# SCH.net
KiCad netlist of a schematic drawn in Altium Designer
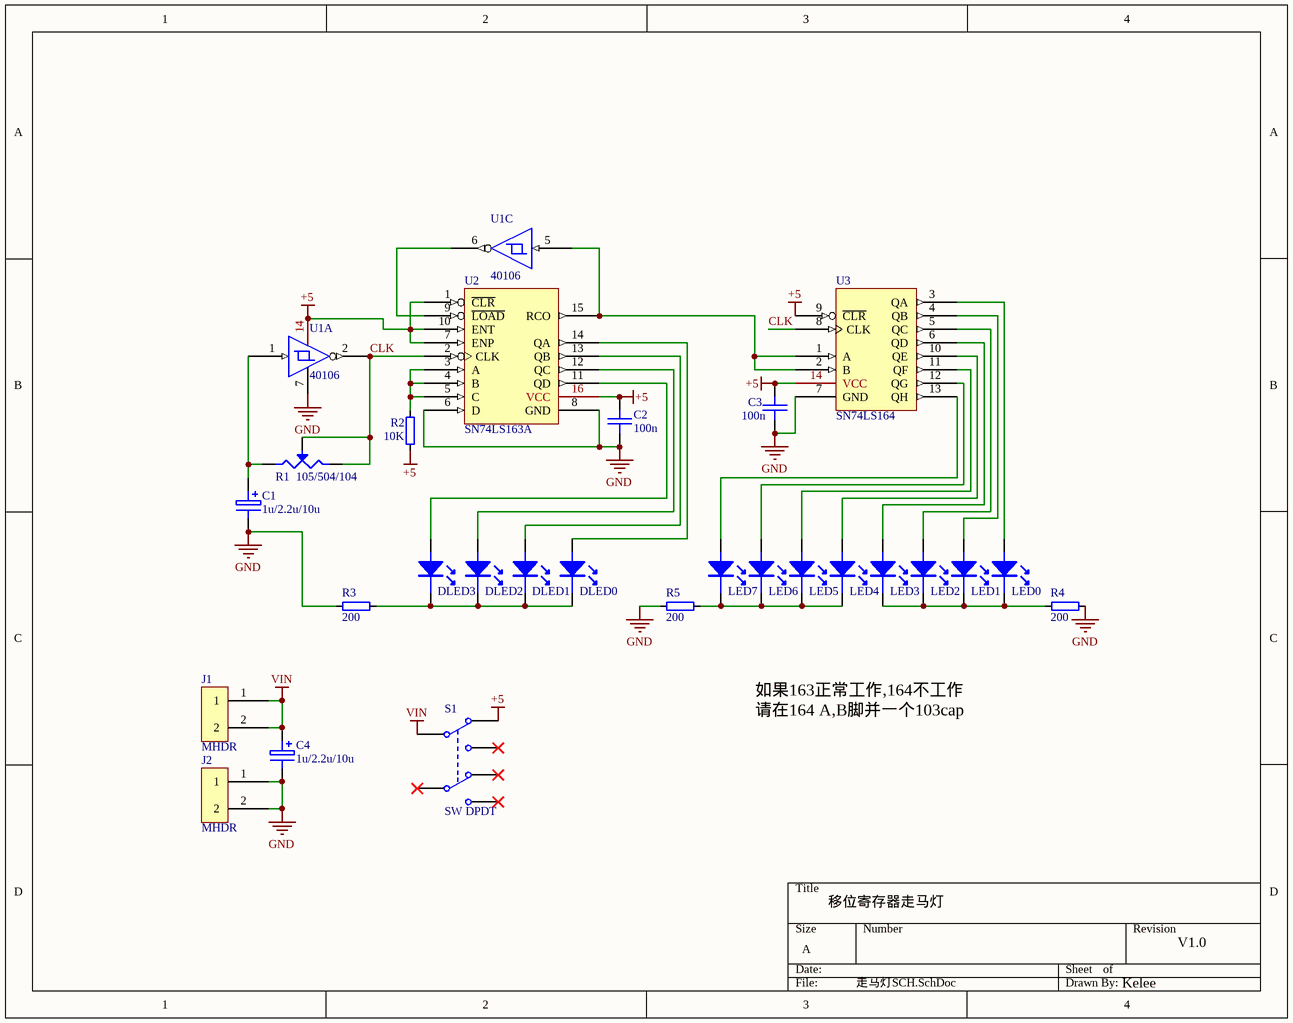
[diagram p0: 走马灯SCH.SchDoc]

(export (version "E")
  (design (tool "Eeschema 10.0.6"))
  (components
    (comp (ref "C1")
      (value "1u/2.2u/10u")
      (footprint "插件电容，贴片电容:C5X8")
      (description "电解电容")
      (libsource (lib "走马灯SCH") (part "CAP-E"))
    )
    (comp (ref "C2")
      (value "100n")
      (footprint "插件电容，贴片电容:MLCC5.08-A")
      (description "独石电容")
      (libsource (lib "走马灯SCH") (part "CAP-M"))
    )
    (comp (ref "C3")
      (value "100n")
      (footprint "插件电容，贴片电容:MLCC5.08-A")
      (description "独石电容")
      (libsource (lib "走马灯SCH") (part "CAP-M"))
    )
    (comp (ref "C4")
      (value "1u/2.2u/10u")
      (footprint "插件电容，贴片电容:C5X8")
      (description "电解电容")
      (libsource (lib "走马灯SCH") (part "CAP-E"))
    )
    (comp (ref "DLED0")
      (value "D-LED")
      (footprint "LED,数码管,显示屏,点阵,蜂鸣器:LED 5MM-Y")
      (description "LED")
      (libsource (lib "走马灯SCH") (part "D-LED"))
    )
    (comp (ref "DLED1")
      (value "D-LED")
      (footprint "LED,数码管,显示屏,点阵,蜂鸣器:LED 5MM-Y")
      (description "LED")
      (libsource (lib "走马灯SCH") (part "D-LED"))
    )
    (comp (ref "DLED2")
      (value "D-LED")
      (footprint "LED,数码管,显示屏,点阵,蜂鸣器:LED 5MM-Y")
      (description "LED")
      (libsource (lib "走马灯SCH") (part "D-LED"))
    )
    (comp (ref "DLED3")
      (value "D-LED")
      (footprint "LED,数码管,显示屏,点阵,蜂鸣器:LED 5MM-Y")
      (description "LED")
      (libsource (lib "走马灯SCH") (part "D-LED"))
    )
    (comp (ref "J1")
      (value "MHDR")
      (footprint "走马灯PCB:HDR1X2")
      (description "MHDR1x2")
      (libsource (lib "走马灯SCH") (part "MHDR1x2"))
    )
    (comp (ref "J2")
      (value "MHDR")
      (footprint "走马灯PCB:HDR1X2")
      (description "MHDR1x2")
      (libsource (lib "走马灯SCH") (part "MHDR1x2"))
    )
    (comp (ref "LED0")
      (value "LED")
      (footprint "LED,数码管,显示屏,点阵,蜂鸣器:LED 5MM-R")
      (libsource (lib "走马灯SCH") (part "LED"))
    )
    (comp (ref "LED1")
      (value "LED")
      (footprint "LED,数码管,显示屏,点阵,蜂鸣器:LED 5MM-R")
      (libsource (lib "走马灯SCH") (part "LED"))
    )
    (comp (ref "LED2")
      (value "LED")
      (footprint "LED,数码管,显示屏,点阵,蜂鸣器:LED 5MM-R")
      (libsource (lib "走马灯SCH") (part "LED"))
    )
    (comp (ref "LED3")
      (value "LED")
      (footprint "LED,数码管,显示屏,点阵,蜂鸣器:LED 5MM-R")
      (libsource (lib "走马灯SCH") (part "LED"))
    )
    (comp (ref "LED4")
      (value "LED")
      (footprint "LED,数码管,显示屏,点阵,蜂鸣器:LED 5MM-R")
      (libsource (lib "走马灯SCH") (part "LED"))
    )
    (comp (ref "LED5")
      (value "LED")
      (footprint "LED,数码管,显示屏,点阵,蜂鸣器:LED 5MM-R")
      (libsource (lib "走马灯SCH") (part "LED"))
    )
    (comp (ref "LED6")
      (value "LED")
      (footprint "LED,数码管,显示屏,点阵,蜂鸣器:LED 5MM-R")
      (libsource (lib "走马灯SCH") (part "LED"))
    )
    (comp (ref "LED7")
      (value "LED")
      (footprint "LED,数码管,显示屏,点阵,蜂鸣器:LED 5MM-R")
      (libsource (lib "走马灯SCH") (part "LED"))
    )
    (comp (ref "R1")
      (value "105/504/104")
      (footprint "电阻插件贴片排阻:RES ADJ3")
      (libsource (lib "走马灯SCH") (part "R-GLIDE"))
    )
    (comp (ref "R2")
      (value "10K")
      (footprint "电阻插件贴片排阻:RS 1/4W")
      (description "resistor")
      (libsource (lib "走马灯SCH") (part "R-10K"))
    )
    (comp (ref "R3")
      (value "200")
      (footprint "电阻插件贴片排阻:RS 1/4W")
      (description "resistor")
      (libsource (lib "走马灯SCH") (part "R-200"))
    )
    (comp (ref "R4")
      (value "200")
      (footprint "电阻插件贴片排阻:RS 1/4W")
      (description "resistor")
      (libsource (lib "走马灯SCH") (part "R-200"))
    )
    (comp (ref "R5")
      (value "200")
      (footprint "电阻插件贴片排阻:RS 1/4W")
      (description "resistor")
      (libsource (lib "走马灯SCH") (part "R-200"))
    )
    (comp (ref "S1")
      (value "SW DPDT")
      (footprint "走马灯PCB:KFT DIP-8X8")
      (description "Switch")
      (fields (field (name "PUBLISHER") "Altium Limited"))
      (libsource (lib "走马灯SCH") (part "SW DPDT"))
    )
    (comp (ref "U1") (value "40106") (footprint "IC:DIP14") (libsource (lib "走马灯SCH") (part "CD40106")))
    (comp (ref "U2")
      (value "SN74LS163A")
      (footprint "IC:DIP16")
      (description "SYN 4-BIT CNT")
      (libsource (lib "走马灯SCH") (part "SN74LS163A"))
    )
    (comp (ref "U3")
      (value "SN74LS164")
      (footprint "IC:DIP14")
      (description "8-BIT PALL SERI SFT REG")
      (libsource (lib "走马灯SCH") (part "SN74LS164"))
    )
  )
  (nets
    (net (code "1") (name "+5") (class "Default")
      (node (ref "C2") (pin "2") (pinfunction "2_2") (pintype "passive"))
      (node (ref "C3") (pin "2") (pinfunction "2_2") (pintype "passive"))
      (node (ref "R2") (pin "2") (pinfunction "2_2") (pintype "passive"))
      (node (ref "S1") (pin "1") (pinfunction "NC1_1") (pintype "passive"))
      (node (ref "U1") (pin "14") (pinfunction "Vdd_14") (pintype "passive"))
      (node (ref "U2") (pin "1") (pinfunction "~{CLR}_1") (pintype "input"))
      (node (ref "U2") (pin "10") (pinfunction "ENT_10") (pintype "input"))
      (node (ref "U2") (pin "16") (pinfunction "VCC_16") (pintype "passive"))
      (node (ref "U2") (pin "7") (pinfunction "ENP_7") (pintype "input"))
      (node (ref "U3") (pin "14") (pinfunction "VCC_14") (pintype "passive"))
      (node (ref "U3") (pin "9") (pinfunction "~{CLR}_9") (pintype "input"))
    )
    (net (code "2") (name "/CLK") (class "Default")
      (node (ref "R1") (pin "2") (pinfunction "2_2") (pintype "passive"))
      (node (ref "R1") (pin "3") (pinfunction "W_3") (pintype "passive"))
      (node (ref "U1") (pin "2") (pintype "output"))
      (node (ref "U2") (pin "2") (pinfunction "CLK_2") (pintype "input"))
      (node (ref "U3") (pin "8") (pinfunction "CLK_8") (pintype "input"))
    )
    (net (code "3") (name "GND") (class "Default")
      (node (ref "C1") (pin "2") (pinfunction "2_2") (pintype "passive"))
      (node (ref "C2") (pin "1") (pinfunction "1_1") (pintype "passive"))
      (node (ref "C3") (pin "1") (pinfunction "1_1") (pintype "passive"))
      (node (ref "C4") (pin "2") (pinfunction "2_2") (pintype "passive"))
      (node (ref "J2") (pin "1") (pinfunction "1_1") (pintype "passive"))
      (node (ref "J2") (pin "2") (pinfunction "2_2") (pintype "passive"))
      (node (ref "R3") (pin "1") (pinfunction "1_1") (pintype "passive"))
      (node (ref "R4") (pin "2") (pinfunction "2_2") (pintype "passive"))
      (node (ref "R5") (pin "1") (pinfunction "1_1") (pintype "passive"))
      (node (ref "U1") (pin "7") (pinfunction "GND_7") (pintype "power_in"))
      (node (ref "U2") (pin "6") (pinfunction "D_6") (pintype "input"))
      (node (ref "U2") (pin "8") (pinfunction "GND_8") (pintype "power_in"))
      (node (ref "U3") (pin "7") (pinfunction "GND_7") (pintype "passive"))
    )
    (net (code "4") (name "Net-(C1-Pad1)") (class "Default")
      (node (ref "C1") (pin "1") (pinfunction "1_1") (pintype "passive"))
      (node (ref "R1") (pin "1") (pinfunction "1_1") (pintype "passive"))
      (node (ref "U1") (pin "1") (pintype "input"))
    )
    (net (code "5") (name "Net-(DLED0-A)") (class "Default")
      (node (ref "DLED0") (pin "1") (pinfunction "A_1") (pintype "passive"))
      (node (ref "U2") (pin "14") (pinfunction "QA_14") (pintype "output"))
    )
    (net (code "6") (name "Net-(DLED0-K)") (class "Default")
      (node (ref "DLED0") (pin "2") (pinfunction "K_2") (pintype "passive"))
      (node (ref "DLED1") (pin "2") (pinfunction "K_2") (pintype "passive"))
      (node (ref "DLED2") (pin "2") (pinfunction "K_2") (pintype "passive"))
      (node (ref "DLED3") (pin "2") (pinfunction "K_2") (pintype "passive"))
      (node (ref "R3") (pin "2") (pinfunction "2_2") (pintype "passive"))
    )
    (net (code "7") (name "Net-(DLED1-A)") (class "Default")
      (node (ref "DLED1") (pin "1") (pinfunction "A_1") (pintype "passive"))
      (node (ref "U2") (pin "13") (pinfunction "QB_13") (pintype "output"))
    )
    (net (code "8") (name "Net-(DLED2-A)") (class "Default")
      (node (ref "DLED2") (pin "1") (pinfunction "A_1") (pintype "passive"))
      (node (ref "U2") (pin "12") (pinfunction "QC_12") (pintype "output"))
    )
    (net (code "9") (name "Net-(DLED3-A)") (class "Default")
      (node (ref "DLED3") (pin "1") (pinfunction "A_1") (pintype "passive"))
      (node (ref "U2") (pin "11") (pinfunction "QD_11") (pintype "output"))
    )
    (net (code "10") (name "Net-(LED0-A)") (class "Default")
      (node (ref "LED0") (pin "1") (pinfunction "A_1") (pintype "passive"))
      (node (ref "U3") (pin "3") (pinfunction "QA_3") (pintype "output"))
    )
    (net (code "11") (name "Net-(LED0-K)") (class "Default")
      (node (ref "LED0") (pin "2") (pinfunction "K_2") (pintype "passive"))
      (node (ref "LED1") (pin "2") (pinfunction "K_2") (pintype "passive"))
      (node (ref "LED2") (pin "2") (pinfunction "K_2") (pintype "passive"))
      (node (ref "LED3") (pin "2") (pinfunction "K_2") (pintype "passive"))
      (node (ref "R4") (pin "1") (pinfunction "1_1") (pintype "passive"))
    )
    (net (code "12") (name "Net-(LED1-A)") (class "Default")
      (node (ref "LED1") (pin "1") (pinfunction "A_1") (pintype "passive"))
      (node (ref "U3") (pin "4") (pinfunction "QB_4") (pintype "output"))
    )
    (net (code "13") (name "Net-(LED2-A)") (class "Default")
      (node (ref "LED2") (pin "1") (pinfunction "A_1") (pintype "passive"))
      (node (ref "U3") (pin "5") (pinfunction "QC_5") (pintype "output"))
    )
    (net (code "14") (name "Net-(LED3-A)") (class "Default")
      (node (ref "LED3") (pin "1") (pinfunction "A_1") (pintype "passive"))
      (node (ref "U3") (pin "6") (pinfunction "QD_6") (pintype "output"))
    )
    (net (code "15") (name "Net-(LED4-A)") (class "Default")
      (node (ref "LED4") (pin "1") (pinfunction "A_1") (pintype "passive"))
      (node (ref "U3") (pin "10") (pinfunction "QE_10") (pintype "output"))
    )
    (net (code "16") (name "Net-(LED4-K)") (class "Default")
      (node (ref "LED4") (pin "2") (pinfunction "K_2") (pintype "passive"))
      (node (ref "LED5") (pin "2") (pinfunction "K_2") (pintype "passive"))
      (node (ref "LED6") (pin "2") (pinfunction "K_2") (pintype "passive"))
      (node (ref "LED7") (pin "2") (pinfunction "K_2") (pintype "passive"))
      (node (ref "R5") (pin "2") (pinfunction "2_2") (pintype "passive"))
    )
    (net (code "17") (name "Net-(LED5-A)") (class "Default")
      (node (ref "LED5") (pin "1") (pinfunction "A_1") (pintype "passive"))
      (node (ref "U3") (pin "11") (pinfunction "QF_11") (pintype "output"))
    )
    (net (code "18") (name "Net-(LED6-A)") (class "Default")
      (node (ref "LED6") (pin "1") (pinfunction "A_1") (pintype "passive"))
      (node (ref "U3") (pin "12") (pinfunction "QG_12") (pintype "output"))
    )
    (net (code "19") (name "Net-(LED7-A)") (class "Default")
      (node (ref "LED7") (pin "1") (pinfunction "A_1") (pintype "passive"))
      (node (ref "U3") (pin "13") (pinfunction "QH_13") (pintype "output"))
    )
    (net (code "20") (name "Net-(U2-A)") (class "Default")
      (node (ref "R2") (pin "1") (pinfunction "1_1") (pintype "passive"))
      (node (ref "U2") (pin "3") (pinfunction "A_3") (pintype "input"))
      (node (ref "U2") (pin "4") (pinfunction "B_4") (pintype "input"))
      (node (ref "U2") (pin "5") (pinfunction "C_5") (pintype "input"))
    )
    (net (code "21") (name "Net-(U2-RCO)") (class "Default")
      (node (ref "U1") (pin "5") (pintype "input"))
      (node (ref "U2") (pin "15") (pinfunction "RCO_15") (pintype "output"))
      (node (ref "U3") (pin "1") (pinfunction "A_1") (pintype "input"))
      (node (ref "U3") (pin "2") (pinfunction "B_2") (pintype "input"))
    )
    (net (code "22") (name "Net-(U2-~{LOAD})") (class "Default")
      (node (ref "U1") (pin "6") (pintype "output"))
      (node (ref "U2") (pin "9") (pinfunction "~{LOAD}_9") (pintype "input"))
    )
    (net (code "23") (name "VCC") (class "Default")
      (node (ref "U1") (pin "14") (pinfunction "VCC_14") (pintype "power_in"))
      (node (ref "U2") (pin "16") (pinfunction "VCC_16") (pintype "power_in"))
      (node (ref "U3") (pin "14") (pinfunction "VCC_14") (pintype "power_in"))
    )
    (net (code "24") (name "VIN") (class "Default")
      (node (ref "C4") (pin "1") (pinfunction "1_1") (pintype "passive"))
      (node (ref "J1") (pin "1") (pinfunction "1_1") (pintype "passive"))
      (node (ref "J1") (pin "2") (pinfunction "2_2") (pintype "passive"))
      (node (ref "S1") (pin "3") (pinfunction "COMMON1_3") (pintype "passive"))
    )
    (net (code "25") (name "unconnected-(S1-COMMON2-Pad6)") (class "Default")
      (node (ref "S1") (pin "6") (pinfunction "COMMON2_6") (pintype "passive+no_connect"))
    )
    (net (code "26") (name "unconnected-(S1-NC2-Pad4)") (class "Default")
      (node (ref "S1") (pin "4") (pinfunction "NC2_4") (pintype "passive+no_connect"))
    )
    (net (code "27") (name "unconnected-(S1-NO1-Pad2)") (class "Default")
      (node (ref "S1") (pin "2") (pinfunction "NO1_2") (pintype "passive+no_connect"))
    )
    (net (code "28") (name "unconnected-(S1-NO2-Pad5)") (class "Default")
      (node (ref "S1") (pin "5") (pinfunction "NO2_5") (pintype "passive+no_connect"))
    )
  )
)
